# weblight.net
KiCad netlist of a schematic drawn in EAGLE
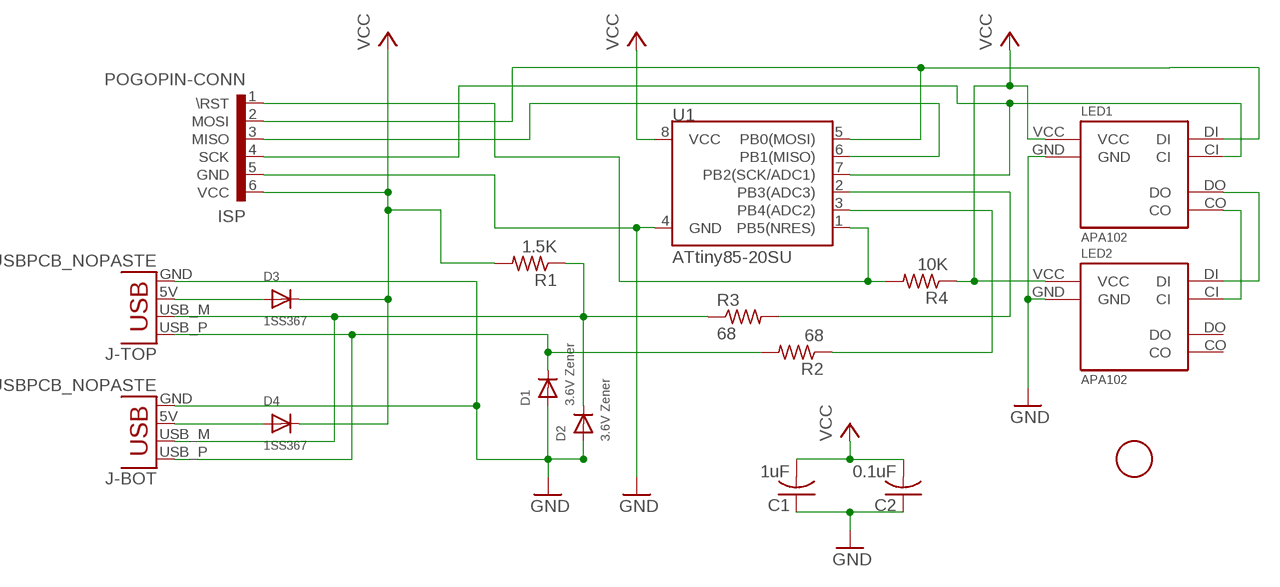
[diagram p0: schematic, sheet 1]

(export (version "E")
  (design (tool "Eeschema 10.0.6"))
  (components
    (comp (ref "C1")
      (value "1uF")
      (footprint "eagle-import:C0805")
      (libsource (lib "eagle-import") (part "C-USC0805"))
    )
    (comp (ref "C2")
      (value "0.1uF")
      (footprint "eagle-import:C0805")
      (libsource (lib "eagle-import") (part "C-USC0805"))
    )
    (comp (ref "D1")
      (value "3.6V Zener")
      (footprint "eagle-import:SOD-323")
      (libsource (lib "eagle-import") (part "DIODESOD-323"))
    )
    (comp (ref "D2")
      (value "3.6V Zener")
      (footprint "eagle-import:SOD-323")
      (libsource (lib "eagle-import") (part "DIODESOD-323"))
    )
    (comp (ref "D3")
      (value "1SS367")
      (footprint "eagle-import:SOD-323")
      (libsource (lib "eagle-import") (part "DIODESOD-323"))
    )
    (comp (ref "D4")
      (value "1SS367")
      (footprint "eagle-import:SOD-323")
      (libsource (lib "eagle-import") (part "DIODESOD-323"))
    )
    (comp (ref "FID1")
      (value "FIDUCIAL")
      (footprint "eagle-import:FIDUCIAL_1MM")
      (libsource (lib "eagle-import") (part "FIDUCIAL"))
    )
    (comp (ref "ISP")
      (value "POGOPIN-CONN")
      (footprint "eagle-import:POGOPROG-CONN-OH-SMALLERVIAS-NOCREAM")
      (libsource (lib "eagle-import") (part "POGOPIN-CONN"))
    )
    (comp (ref "J-BOT")
      (value "USBPCB_NOPASTE")
      (footprint "eagle-import:USB-A-PCB-NOPASTE")
      (libsource (lib "eagle-import") (part "USBPCB_NOPASTE"))
    )
    (comp (ref "J-TOP")
      (value "USBPCB_NOPASTE")
      (footprint "eagle-import:USB-A-PCB-NOPASTE")
      (libsource (lib "eagle-import") (part "USBPCB_NOPASTE"))
    )
    (comp (ref "LED1")
      (value "APA102")
      (footprint "eagle-import:APA102")
      (libsource (lib "eagle-import") (part "APA102"))
    )
    (comp (ref "LED2")
      (value "APA102")
      (footprint "eagle-import:APA102")
      (libsource (lib "eagle-import") (part "APA102"))
    )
    (comp (ref "R1")
      (value "1.5K")
      (footprint "eagle-import:R0805")
      (libsource (lib "eagle-import") (part "R-US_R0805"))
    )
    (comp (ref "R2")
      (value "68")
      (footprint "eagle-import:R0805")
      (libsource (lib "eagle-import") (part "R-US_R0805"))
    )
    (comp (ref "R3")
      (value "68")
      (footprint "eagle-import:R0805")
      (libsource (lib "eagle-import") (part "R-US_R0805"))
    )
    (comp (ref "R4")
      (value "10K")
      (footprint "eagle-import:R0805")
      (libsource (lib "eagle-import") (part "R-US_R0805"))
    )
    (comp (ref "U1")
      (value "ATtiny85-20SU")
      (footprint "eagle-import:SO08-EIAJ")
      (libsource (lib "eagle-import") (part "ATTINY45TINY85-20-SMT"))
    )
  )
  (nets
    (net (code "1") (name "GND") (class "Default")
      (node (ref "C1") (pin "1") (pinfunction "1_1") (pintype "passive"))
      (node (ref "C2") (pin "1") (pinfunction "1_1") (pintype "passive"))
      (node (ref "D1") (pin "A") (pinfunction "A_A") (pintype "passive"))
      (node (ref "D2") (pin "A") (pinfunction "A_A") (pintype "passive"))
      (node (ref "ISP") (pin "5") (pinfunction "GND_5") (pintype "bidirectional"))
      (node (ref "J-BOT") (pin "GND") (pinfunction "GND_GND") (pintype "bidirectional"))
      (node (ref "J-TOP") (pin "GND") (pinfunction "GND_GND") (pintype "bidirectional"))
      (node (ref "LED1") (pin "GND") (pinfunction "GND_GND") (pintype "power_in"))
      (node (ref "LED2") (pin "GND") (pinfunction "GND_GND") (pintype "power_in"))
      (node (ref "U1") (pin "4") (pinfunction "GND_4") (pintype "bidirectional"))
    )
    (net (code "2") (name "Net-(ISP-MISO)") (class "Default")
      (node (ref "ISP") (pin "3") (pinfunction "MISO_3") (pintype "bidirectional"))
      (node (ref "U1") (pin "6") (pinfunction "PB1(MISO)_6") (pintype "bidirectional"))
    )
    (net (code "3") (name "Net-(ISP-MOSI)") (class "Default")
      (node (ref "ISP") (pin "2") (pinfunction "MOSI_2") (pintype "bidirectional"))
      (node (ref "LED1") (pin "DI") (pinfunction "DI_DI") (pintype "input"))
      (node (ref "U1") (pin "5") (pinfunction "PB0(MOSI)_5") (pintype "bidirectional"))
    )
    (net (code "4") (name "Net-(ISP-SCK)") (class "Default")
      (node (ref "ISP") (pin "4") (pinfunction "SCK_4") (pintype "bidirectional"))
      (node (ref "LED1") (pin "CI") (pinfunction "CI_CI") (pintype "input"))
      (node (ref "U1") (pin "7") (pinfunction "PB2(SCK/ADC1)_7") (pintype "bidirectional"))
    )
    (net (code "5") (name "Net-(ISP-\\RST)") (class "Default")
      (node (ref "ISP") (pin "1") (pinfunction "\\RST_1") (pintype "bidirectional"))
      (node (ref "R4") (pin "2") (pinfunction "2_2") (pintype "passive"))
      (node (ref "U1") (pin "1") (pinfunction "PB5(NRES)_1") (pintype "bidirectional"))
    )
    (net (code "6") (name "Net-(J-BOT-D+)") (class "Default")
      (node (ref "D1") (pin "C") (pinfunction "C_C") (pintype "passive"))
      (node (ref "J-BOT") (pin "USB_P") (pinfunction "D+_USB_P") (pintype "bidirectional"))
      (node (ref "J-TOP") (pin "USB_P") (pinfunction "D+_USB_P") (pintype "bidirectional"))
      (node (ref "R2") (pin "2") (pinfunction "2_2") (pintype "passive"))
    )
    (net (code "7") (name "Net-(J-BOT-D-)") (class "Default")
      (node (ref "D2") (pin "C") (pinfunction "C_C") (pintype "passive"))
      (node (ref "J-BOT") (pin "USB_M") (pinfunction "D-_USB_M") (pintype "bidirectional"))
      (node (ref "J-TOP") (pin "USB_M") (pinfunction "D-_USB_M") (pintype "bidirectional"))
      (node (ref "R1") (pin "1") (pinfunction "1_1") (pintype "passive"))
      (node (ref "R3") (pin "1") (pinfunction "1_1") (pintype "passive"))
    )
    (net (code "8") (name "Net-(J-BOT-VBUS)") (class "Default")
      (node (ref "D4") (pin "A") (pinfunction "A_A") (pintype "passive"))
      (node (ref "J-BOT") (pin "5V") (pinfunction "VBUS_5V") (pintype "bidirectional"))
    )
    (net (code "9") (name "Net-(J-TOP-VBUS)") (class "Default")
      (node (ref "D3") (pin "A") (pinfunction "A_A") (pintype "passive"))
      (node (ref "J-TOP") (pin "5V") (pinfunction "VBUS_5V") (pintype "bidirectional"))
    )
    (net (code "10") (name "Net-(LED1-PadCO)") (class "Default")
      (node (ref "LED1") (pin "CO") (pinfunction "CO_CO") (pintype "output"))
      (node (ref "LED2") (pin "CI") (pinfunction "CI_CI") (pintype "input"))
    )
    (net (code "11") (name "Net-(LED1-PadDO)") (class "Default")
      (node (ref "LED1") (pin "DO") (pinfunction "DO_DO") (pintype "output"))
      (node (ref "LED2") (pin "DI") (pinfunction "DI_DI") (pintype "input"))
    )
    (net (code "12") (name "Net-(U1-PB3(ADC3))") (class "Default")
      (node (ref "R3") (pin "2") (pinfunction "2_2") (pintype "passive"))
      (node (ref "U1") (pin "2") (pinfunction "PB3(ADC3)_2") (pintype "bidirectional"))
    )
    (net (code "13") (name "Net-(U1-PB4(ADC2))") (class "Default")
      (node (ref "R2") (pin "1") (pinfunction "1_1") (pintype "passive"))
      (node (ref "U1") (pin "3") (pinfunction "PB4(ADC2)_3") (pintype "bidirectional"))
    )
    (net (code "14") (name "VCC") (class "Default")
      (node (ref "C1") (pin "2") (pinfunction "2_2") (pintype "passive"))
      (node (ref "C2") (pin "2") (pinfunction "2_2") (pintype "passive"))
      (node (ref "D3") (pin "C") (pinfunction "C_C") (pintype "passive"))
      (node (ref "D4") (pin "C") (pinfunction "C_C") (pintype "passive"))
      (node (ref "ISP") (pin "6") (pinfunction "VCC_6") (pintype "bidirectional"))
      (node (ref "LED1") (pin "VCC") (pinfunction "VCC_VCC") (pintype "power_in"))
      (node (ref "LED2") (pin "VCC") (pinfunction "VCC_VCC") (pintype "power_in"))
      (node (ref "R1") (pin "2") (pinfunction "2_2") (pintype "passive"))
      (node (ref "R4") (pin "1") (pinfunction "1_1") (pintype "passive"))
      (node (ref "U1") (pin "8") (pinfunction "VCC_8") (pintype "bidirectional"))
    )
    (net (code "15") (name "unconnected-(LED2-PadCO)") (class "Default")
      (node (ref "LED2") (pin "CO") (pinfunction "CO_CO") (pintype "output"))
    )
    (net (code "16") (name "unconnected-(LED2-PadDO)") (class "Default")
      (node (ref "LED2") (pin "DO") (pinfunction "DO_DO") (pintype "output"))
    )
  )
)
